# geiger_fixedR5R6.net
KiCad netlist of a schematic drawn in EAGLE
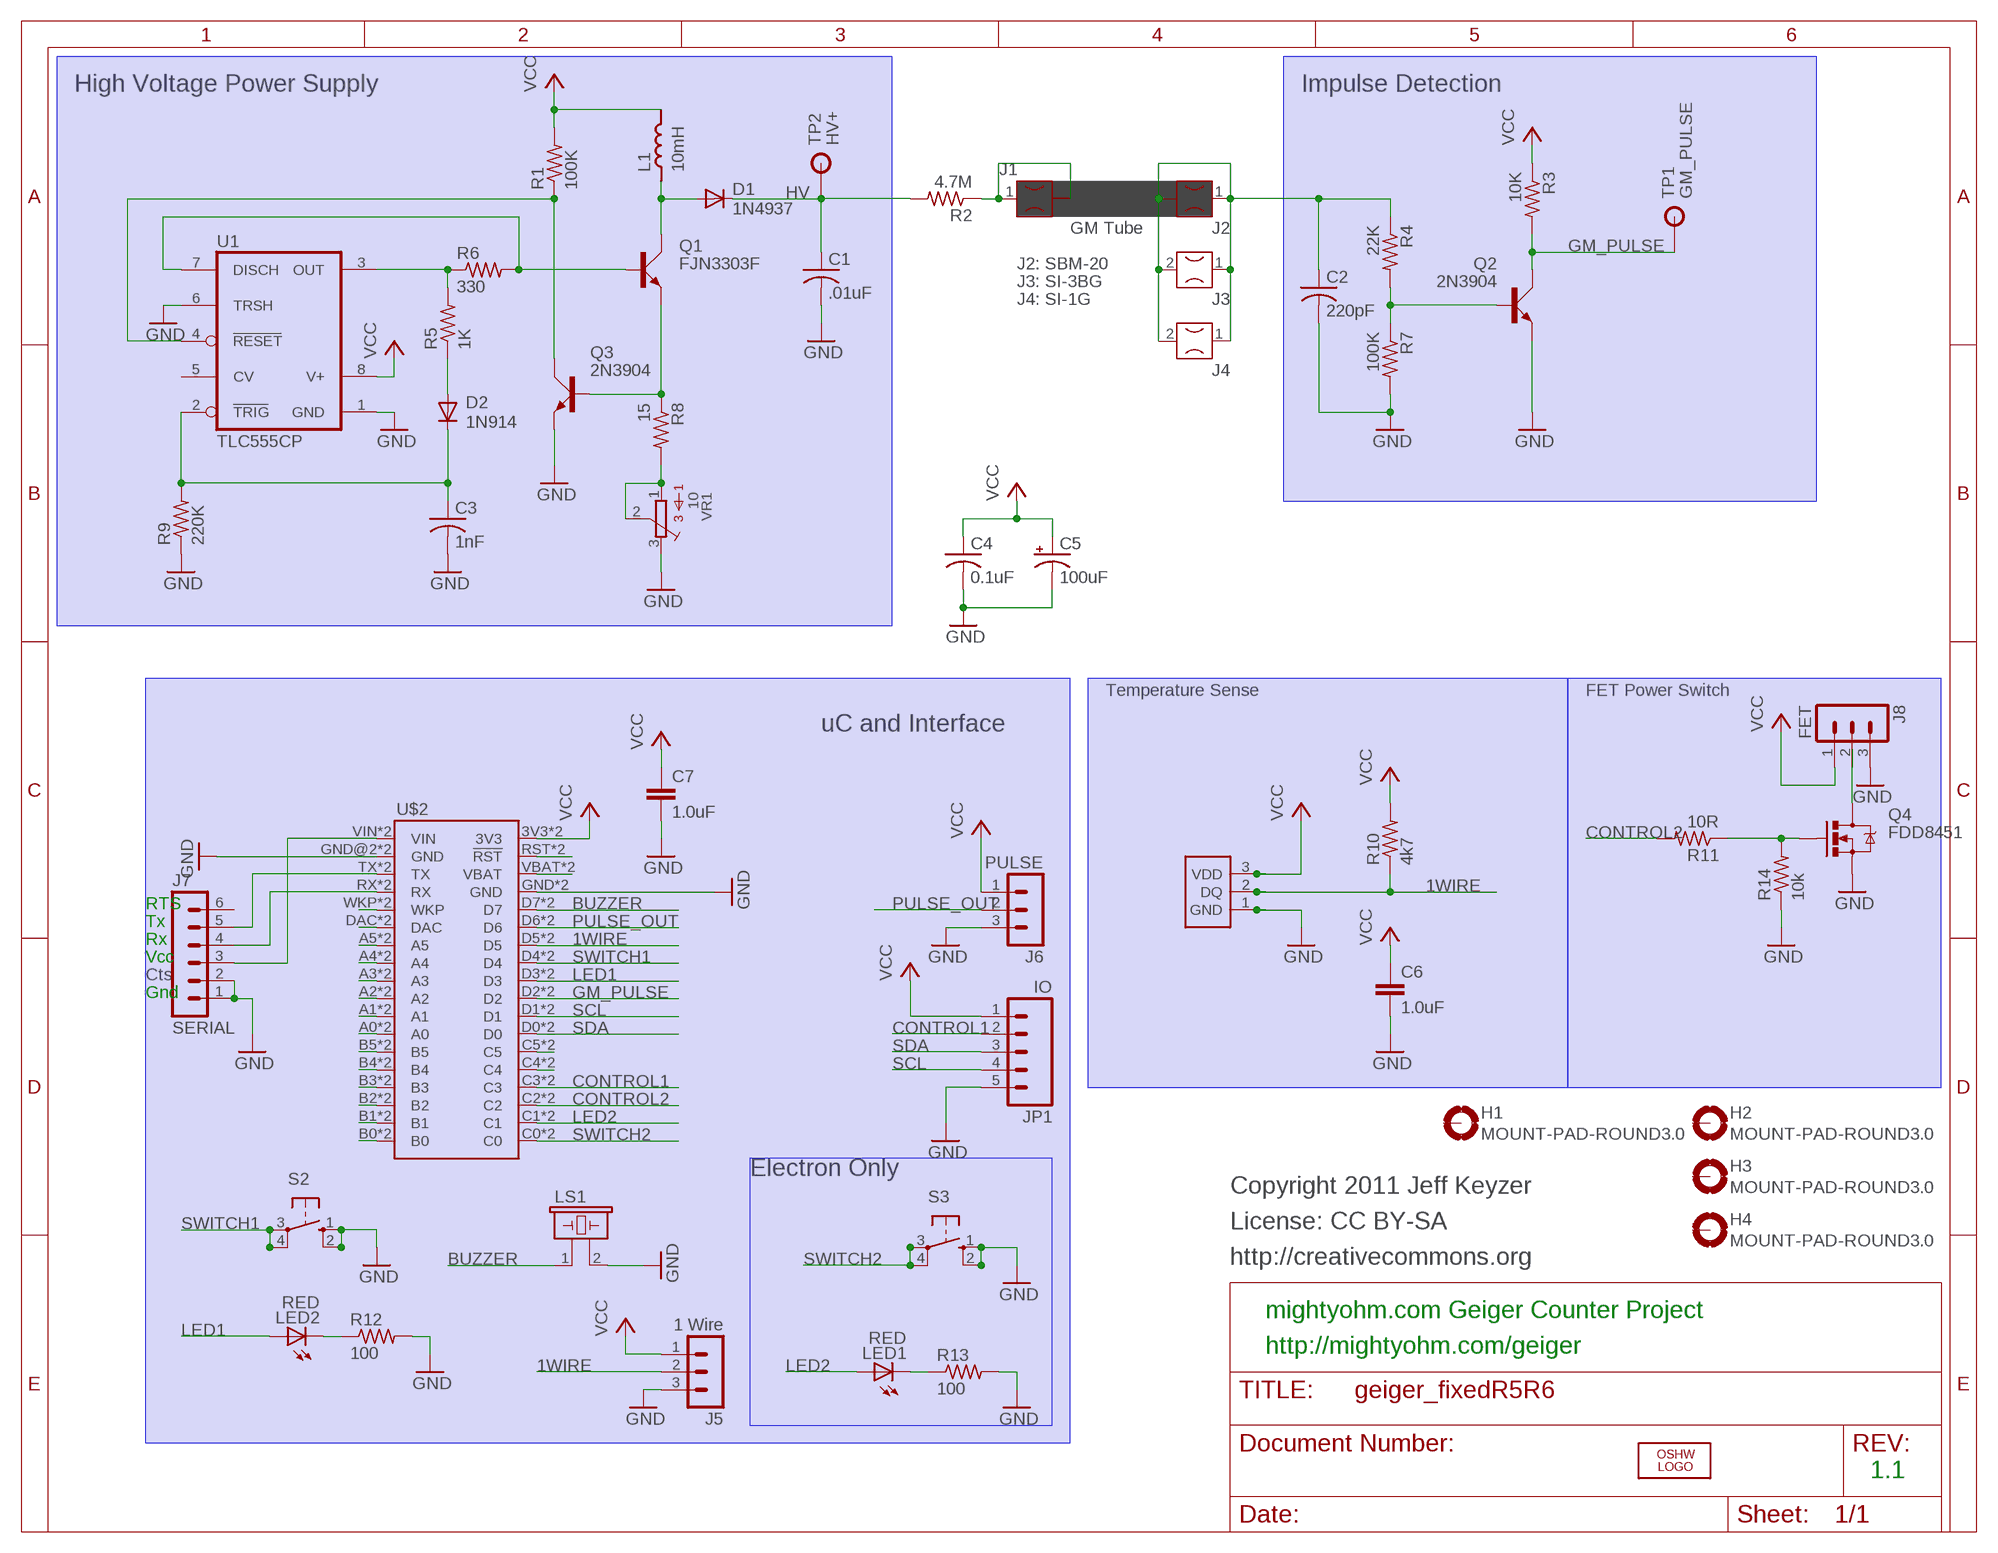
[diagram p0: schematic, sheet 1]

(export (version "E")
  (design (tool "Eeschema 10.0.6"))
  (components
    (comp (ref "C1")
      (value ".01uF")
      (footprint "eagle-import:C102-043X133")
      (libsource (lib "eagle-import") (part "C-US102-043X133"))
    )
    (comp (ref "C2")
      (value "220pF")
      (footprint "eagle-import:C050-030X075")
      (libsource (lib "eagle-import") (part "C-US050-030X075"))
    )
    (comp (ref "C3")
      (value "1nF")
      (footprint "eagle-import:C050-025X075")
      (libsource (lib "eagle-import") (part "C-US050-025X075"))
    )
    (comp (ref "C4")
      (value "0.1uF")
      (footprint "eagle-import:C025-025X050")
      (libsource (lib "eagle-import") (part "C-US025-025X050"))
    )
    (comp (ref "C5")
      (value "100uF")
      (footprint "eagle-import:E2,5-6")
      (libsource (lib "eagle-import") (part "CPOL-USE2.5-6"))
    )
    (comp (ref "C6")
      (value "1.0uF")
      (footprint "eagle-import:0805-CAP")
      (libsource (lib "eagle-import") (part "1.0UF-25V-+80/-20(0805){dblquote}"))
    )
    (comp (ref "C7")
      (value "1.0uF")
      (footprint "eagle-import:0805-CAP")
      (libsource (lib "eagle-import") (part "1.0UF-25V-+80/-20(0805){dblquote}"))
    )
    (comp (ref "D1")
      (value "1N4937")
      (footprint "eagle-import:DO41-10")
      (libsource (lib "eagle-import") (part "1N4933"))
    )
    (comp (ref "D2")
      (value "1N914")
      (footprint "eagle-import:DO35-7")
      (libsource (lib "eagle-import") (part "1N4148DO35-7"))
    )
    (comp (ref "H1")
      (value "MOUNT-PAD-ROUND3.0")
      (footprint "eagle-import:3,0-PAD")
      (libsource (lib "eagle-import") (part "MOUNT-PAD-ROUND3.0"))
    )
    (comp (ref "H2")
      (value "MOUNT-PAD-ROUND3.0")
      (footprint "eagle-import:3,0-PAD")
      (libsource (lib "eagle-import") (part "MOUNT-PAD-ROUND3.0"))
    )
    (comp (ref "H3")
      (value "MOUNT-PAD-ROUND3.0")
      (footprint "eagle-import:3,0-PAD")
      (libsource (lib "eagle-import") (part "MOUNT-PAD-ROUND3.0"))
    )
    (comp (ref "H4")
      (value "MOUNT-PAD-ROUND3.0")
      (footprint "eagle-import:3,0-PAD")
      (libsource (lib "eagle-import") (part "MOUNT-PAD-ROUND3.0"))
    )
    (comp (ref "J1")
      (value "FUSECLIPPCMOUNT")
      (footprint "eagle-import:FUSECLIP_PCMOUNT")
      (libsource (lib "eagle-import") (part "FUSECLIPPCMOUNT"))
    )
    (comp (ref "J2")
      (value "FUSECLIPPCMOUNT")
      (footprint "eagle-import:FUSECLIP_PCMOUNT")
      (libsource (lib "eagle-import") (part "FUSECLIPPCMOUNT"))
    )
    (comp (ref "J3")
      (value "FUSECLIPPCMOUNT")
      (footprint "eagle-import:FUSECLIP_PCMOUNT")
      (libsource (lib "eagle-import") (part "FUSECLIPPCMOUNT"))
    )
    (comp (ref "J4")
      (value "FUSECLIPPCMOUNT")
      (footprint "eagle-import:FUSECLIP_PCMOUNT")
      (libsource (lib "eagle-import") (part "FUSECLIPPCMOUNT"))
    )
    (comp (ref "J5")
      (value "1 Wire")
      (footprint "eagle-import:MA03-1")
      (libsource (lib "eagle-import") (part "MA03-1"))
    )
    (comp (ref "J6")
      (value "PULSE")
      (footprint "eagle-import:MA03-1")
      (libsource (lib "eagle-import") (part "MA03-1"))
    )
    (comp (ref "J7")
      (value "SERIAL")
      (footprint "eagle-import:MA06-1")
      (libsource (lib "eagle-import") (part "MA06-1"))
    )
    (comp (ref "J8")
      (value "FET")
      (footprint "eagle-import:MA03-1")
      (libsource (lib "eagle-import") (part "MA03-1"))
    )
    (comp (ref "JP1")
      (value "IO")
      (footprint "eagle-import:1X05")
      (libsource (lib "eagle-import") (part "M05PTH"))
    )
    (comp (ref "L1")
      (value "10mH")
      (footprint "eagle-import:ELC09D")
      (libsource (lib "eagle-import") (part "INDELC09D"))
    )
    (comp (ref "LED1")
      (value "RED")
      (footprint "eagle-import:LED5MM")
      (libsource (lib "eagle-import") (part "LED5MM"))
    )
    (comp (ref "LED2")
      (value "RED")
      (footprint "eagle-import:LED5MM")
      (libsource (lib "eagle-import") (part "LED5MM"))
    )
    (comp (ref "LOGO1")
      (value "OSHW_LOGO_FILLX0200-NT")
      (footprint "eagle-import:OSHW_FILLX200_NOTEXT")
      (libsource (lib "eagle-import") (part "OSHW_LOGO_FILLX0200-NT"))
    )
    (comp (ref "LS1")
      (value "PIEZO17MM")
      (footprint "eagle-import:PS1740P02E")
      (libsource (lib "eagle-import") (part "PIEZO17MM"))
    )
    (comp (ref "Q1")
      (value "FJN3303F")
      (footprint "eagle-import:TO92C")
      (libsource (lib "eagle-import") (part "2N3704"))
    )
    (comp (ref "Q2")
      (value "2N3904")
      (footprint "eagle-import:TO92D")
      (libsource (lib "eagle-import") (part "2N3904"))
    )
    (comp (ref "Q3")
      (value "2N3904")
      (footprint "eagle-import:TO92D")
      (libsource (lib "eagle-import") (part "2N3904"))
    )
    (comp (ref "Q4")
      (value "FDD8451")
      (footprint "eagle-import:DPAK")
      (libsource (lib "eagle-import") (part "MOSFET-NCHANNELFDD8780"))
    )
    (comp (ref "R1")
      (value "100K")
      (footprint "eagle-import:0207_10")
      (libsource (lib "eagle-import") (part "R-US_0207/10"))
    )
    (comp (ref "R2")
      (value "4.7M")
      (footprint "eagle-import:0207_10")
      (libsource (lib "eagle-import") (part "R-US_0207/10"))
    )
    (comp (ref "R3")
      (value "10K")
      (footprint "eagle-import:0207_10")
      (libsource (lib "eagle-import") (part "R-US_0207/10"))
    )
    (comp (ref "R4")
      (value "22K")
      (footprint "eagle-import:0207_10")
      (libsource (lib "eagle-import") (part "R-US_0207/10"))
    )
    (comp (ref "R5")
      (value "1K")
      (footprint "eagle-import:0207_10")
      (libsource (lib "eagle-import") (part "R-US_0207/10"))
    )
    (comp (ref "R6")
      (value "330")
      (footprint "eagle-import:0207_10")
      (libsource (lib "eagle-import") (part "R-US_0207/10"))
    )
    (comp (ref "R7")
      (value "100K")
      (footprint "eagle-import:0207_10")
      (libsource (lib "eagle-import") (part "R-US_0207/10"))
    )
    (comp (ref "R8")
      (value "15")
      (footprint "eagle-import:0207_10")
      (libsource (lib "eagle-import") (part "R-US_0207/10"))
    )
    (comp (ref "R9")
      (value "220K")
      (footprint "eagle-import:0207_10")
      (libsource (lib "eagle-import") (part "R-US_0207/10"))
    )
    (comp (ref "R10")
      (value "4k7")
      (footprint "eagle-import:R0805")
      (libsource (lib "eagle-import") (part "R-US_R0805"))
    )
    (comp (ref "R11")
      (value "10R")
      (footprint "eagle-import:R0805")
      (libsource (lib "eagle-import") (part "R-US_R0805"))
    )
    (comp (ref "R12")
      (value "100")
      (footprint "eagle-import:R0805")
      (libsource (lib "eagle-import") (part "R-US_R0805"))
    )
    (comp (ref "R13")
      (value "100")
      (footprint "eagle-import:R0805")
      (libsource (lib "eagle-import") (part "R-US_R0805"))
    )
    (comp (ref "R14")
      (value "10k")
      (footprint "eagle-import:R0805")
      (libsource (lib "eagle-import") (part "R-US_R0805"))
    )
    (comp (ref "S1")
      (value "DB18B20+")
      (footprint "eagle-import:TO-92-TRIANGLE")
      (libsource (lib "eagle-import") (part "SENSOR-DS18B20"))
    )
    (comp (ref "S2")
      (value "10-XX")
      (footprint "eagle-import:B3F-10XX")
      (libsource (lib "eagle-import") (part "10-XX"))
    )
    (comp (ref "S3")
      (value "10-XX")
      (footprint "eagle-import:B3F-10XX")
      (libsource (lib "eagle-import") (part "10-XX"))
    )
    (comp (ref "TP1")
      (value "GM_PULSE")
      (footprint "eagle-import:TP_PTH")
      (libsource (lib "eagle-import") (part "TPPTH"))
    )
    (comp (ref "TP2")
      (value "HV+")
      (footprint "eagle-import:TP_PTH")
      (libsource (lib "eagle-import") (part "TPPTH"))
    )
    (comp (ref "U$2")
      (value "ELECTRONDUALNAMED")
      (footprint "eagle-import:ELECTRON_SIMPLE_SILK_NAMES_DUAL")
      (libsource (lib "eagle-import") (part "ELECTRONDUALNAMED"))
    )
    (comp (ref "U1")
      (value "TLC555CP")
      (footprint "eagle-import:DIL08")
      (libsource (lib "eagle-import") (part "ICM7555"))
    )
    (comp (ref "VR1")
      (value "10")
      (footprint "eagle-import:3386P")
      (libsource (lib "eagle-import") (part "3386-P"))
    )
  )
  (nets
    (net (code "1") (name "/1WIRE") (class "Default")
      (node (ref "J5") (pin "2") (pinfunction "2_2") (pintype "passive"))
      (node (ref "R10") (pin "1") (pinfunction "1_1") (pintype "passive"))
      (node (ref "S1") (pin "2") (pinfunction "DQ_2") (pintype "bidirectional"))
      (node (ref "U$2") (pin "D5") (pinfunction "D5_D5") (pintype "bidirectional"))
      (node (ref "U$2") (pin "D5_1") (pinfunction "D5_D5_1") (pintype "bidirectional"))
    )
    (net (code "2") (name "/BUZZER") (class "Default")
      (node (ref "LS1") (pin "1") (pinfunction "1_1") (pintype "passive"))
      (node (ref "U$2") (pin "D7") (pinfunction "D7_D7") (pintype "bidirectional"))
      (node (ref "U$2") (pin "D7_1") (pinfunction "D7_D7_1") (pintype "bidirectional"))
    )
    (net (code "3") (name "/CONTROL1") (class "Default")
      (node (ref "JP1") (pin "2") (pinfunction "2_2") (pintype "passive"))
      (node (ref "U$2") (pin "C3") (pinfunction "C3_C3") (pintype "bidirectional"))
      (node (ref "U$2") (pin "C3_1") (pinfunction "C3_C3_1") (pintype "bidirectional"))
    )
    (net (code "4") (name "/CONTROL2") (class "Default")
      (node (ref "R11") (pin "2") (pinfunction "2_2") (pintype "passive"))
      (node (ref "U$2") (pin "C2") (pinfunction "C2_C2") (pintype "bidirectional"))
      (node (ref "U$2") (pin "C2_1") (pinfunction "C2_C2_1") (pintype "bidirectional"))
    )
    (net (code "5") (name "/GM_PULSE") (class "Default")
      (node (ref "Q2") (pin "C") (pinfunction "C_C") (pintype "passive"))
      (node (ref "R3") (pin "2") (pinfunction "2_2") (pintype "passive"))
      (node (ref "TP1") (pin "P$1") (pinfunction "TP_P$1") (pintype "bidirectional"))
      (node (ref "U$2") (pin "D2") (pinfunction "D2_D2") (pintype "bidirectional"))
      (node (ref "U$2") (pin "D2_1") (pinfunction "D2_D2_1") (pintype "bidirectional"))
    )
    (net (code "6") (name "/HV") (class "Default")
      (node (ref "C1") (pin "1") (pinfunction "1_1") (pintype "passive"))
      (node (ref "D1") (pin "C") (pinfunction "C_C") (pintype "passive"))
      (node (ref "R2") (pin "2") (pinfunction "2_2") (pintype "passive"))
      (node (ref "TP2") (pin "P$1") (pinfunction "TP_P$1") (pintype "bidirectional"))
    )
    (net (code "7") (name "/LED1") (class "Default")
      (node (ref "LED2") (pin "A") (pinfunction "A_A") (pintype "passive"))
      (node (ref "U$2") (pin "D3") (pinfunction "D3_D3") (pintype "bidirectional"))
      (node (ref "U$2") (pin "D3_1") (pinfunction "D3_D3_1") (pintype "bidirectional"))
    )
    (net (code "8") (name "/LED2") (class "Default")
      (node (ref "LED1") (pin "A") (pinfunction "A_A") (pintype "passive"))
      (node (ref "U$2") (pin "C1") (pinfunction "C1_C1") (pintype "bidirectional"))
      (node (ref "U$2") (pin "C1_1") (pinfunction "C1_C1_1") (pintype "bidirectional"))
    )
    (net (code "9") (name "/PULSE_OUT") (class "Default")
      (node (ref "J6") (pin "2") (pinfunction "2_2") (pintype "passive"))
      (node (ref "U$2") (pin "D6") (pinfunction "D6_D6") (pintype "bidirectional"))
      (node (ref "U$2") (pin "D6_1") (pinfunction "D6_D6_1") (pintype "bidirectional"))
    )
    (net (code "10") (name "/SCL") (class "Default")
      (node (ref "JP1") (pin "4") (pinfunction "4_4") (pintype "passive"))
      (node (ref "U$2") (pin "D1") (pinfunction "D1_D1") (pintype "bidirectional"))
      (node (ref "U$2") (pin "D1_1") (pinfunction "D1_D1_1") (pintype "bidirectional"))
    )
    (net (code "11") (name "/SDA") (class "Default")
      (node (ref "JP1") (pin "3") (pinfunction "3_3") (pintype "passive"))
      (node (ref "U$2") (pin "D0") (pinfunction "D0_D0") (pintype "bidirectional"))
      (node (ref "U$2") (pin "D0_1") (pinfunction "D0_D0_1") (pintype "bidirectional"))
    )
    (net (code "12") (name "/SWITCH1") (class "Default")
      (node (ref "S2") (pin "3") (pinfunction "P_3") (pintype "passive"))
      (node (ref "S2") (pin "4") (pinfunction "P1_4") (pintype "passive"))
      (node (ref "U$2") (pin "D4") (pinfunction "D4_D4") (pintype "bidirectional"))
      (node (ref "U$2") (pin "D4_1") (pinfunction "D4_D4_1") (pintype "bidirectional"))
    )
    (net (code "13") (name "/SWITCH2") (class "Default")
      (node (ref "S3") (pin "3") (pinfunction "P_3") (pintype "passive"))
      (node (ref "S3") (pin "4") (pinfunction "P1_4") (pintype "passive"))
      (node (ref "U$2") (pin "C0") (pinfunction "C0_C0") (pintype "bidirectional"))
      (node (ref "U$2") (pin "C0_1") (pinfunction "C0_C0_1") (pintype "bidirectional"))
    )
    (net (code "14") (name "GND") (class "Default")
      (node (ref "C1") (pin "2") (pinfunction "2_2") (pintype "passive"))
      (node (ref "C2") (pin "2") (pinfunction "2_2") (pintype "passive"))
      (node (ref "C3") (pin "2") (pinfunction "2_2") (pintype "passive"))
      (node (ref "C4") (pin "2") (pinfunction "2_2") (pintype "passive"))
      (node (ref "C5") (pin "-") (pinfunction "-_-") (pintype "passive"))
      (node (ref "C6") (pin "2") (pinfunction "2_2") (pintype "passive"))
      (node (ref "C7") (pin "2") (pinfunction "2_2") (pintype "passive"))
      (node (ref "J5") (pin "3") (pinfunction "3_3") (pintype "passive"))
      (node (ref "J6") (pin "3") (pinfunction "3_3") (pintype "passive"))
      (node (ref "J7") (pin "1") (pinfunction "1_1") (pintype "passive"))
      (node (ref "J7") (pin "2") (pinfunction "2_2") (pintype "passive"))
      (node (ref "J8") (pin "3") (pinfunction "3_3") (pintype "passive"))
      (node (ref "JP1") (pin "5") (pinfunction "5_5") (pintype "passive"))
      (node (ref "LS1") (pin "2") (pinfunction "2_2") (pintype "passive"))
      (node (ref "Q2") (pin "E") (pinfunction "E_E") (pintype "passive"))
      (node (ref "Q3") (pin "E") (pinfunction "E_E") (pintype "passive"))
      (node (ref "Q4") (pin "3") (pinfunction "S_3") (pintype "passive"))
      (node (ref "R12") (pin "2") (pinfunction "2_2") (pintype "passive"))
      (node (ref "R13") (pin "2") (pinfunction "2_2") (pintype "passive"))
      (node (ref "R14") (pin "1") (pinfunction "1_1") (pintype "passive"))
      (node (ref "R7") (pin "2") (pinfunction "2_2") (pintype "passive"))
      (node (ref "R9") (pin "1") (pinfunction "1_1") (pintype "passive"))
      (node (ref "S1") (pin "1") (pinfunction "GND_1") (pintype "bidirectional"))
      (node (ref "S2") (pin "1") (pinfunction "S_1") (pintype "passive"))
      (node (ref "S2") (pin "2") (pinfunction "S1_2") (pintype "passive"))
      (node (ref "S3") (pin "1") (pinfunction "S_1") (pintype "passive"))
      (node (ref "S3") (pin "2") (pinfunction "S1_2") (pintype "passive"))
      (node (ref "U$2") (pin "GND") (pinfunction "GND_GND") (pintype "power_in"))
      (node (ref "U$2") (pin "GND@2") (pinfunction "GND_GND@2") (pintype "power_in"))
      (node (ref "U$2") (pin "GND_1") (pinfunction "GND_GND_1") (pintype "power_in"))
      (node (ref "U$2") (pin "GND_1B") (pinfunction "GND_GND_1B") (pintype "power_in"))
      (node (ref "U1") (pin "1") (pinfunction "GND_1") (pintype "power_in"))
      (node (ref "U1") (pin "6") (pinfunction "TRSH_6") (pintype "input"))
      (node (ref "VR1") (pin "3") (pinfunction "3_3") (pintype "passive"))
    )
    (net (code "15") (name "Net-(C2-Pad1)") (class "Default")
      (node (ref "C2") (pin "1") (pinfunction "1_1") (pintype "passive"))
      (node (ref "J2") (pin "1") (pinfunction "1_1") (pintype "bidirectional"))
      (node (ref "J2") (pin "2") (pinfunction "2_2") (pintype "bidirectional"))
      (node (ref "J3") (pin "1") (pinfunction "1_1") (pintype "bidirectional"))
      (node (ref "J3") (pin "2") (pinfunction "2_2") (pintype "bidirectional"))
      (node (ref "J4") (pin "1") (pinfunction "1_1") (pintype "bidirectional"))
      (node (ref "J4") (pin "2") (pinfunction "2_2") (pintype "bidirectional"))
      (node (ref "R4") (pin "1") (pinfunction "1_1") (pintype "passive"))
    )
    (net (code "16") (name "Net-(D1-PadA)") (class "Default")
      (node (ref "D1") (pin "A") (pinfunction "A_A") (pintype "passive"))
      (node (ref "L1") (pin "1") (pinfunction "1_1") (pintype "passive"))
      (node (ref "Q1") (pin "C") (pinfunction "C_C") (pintype "passive"))
    )
    (net (code "17") (name "Net-(D2-PadA)") (class "Default")
      (node (ref "D2") (pin "A") (pinfunction "A_A") (pintype "passive"))
      (node (ref "R5") (pin "1") (pinfunction "1_1") (pintype "passive"))
    )
    (net (code "18") (name "Net-(J1-Pad1)") (class "Default")
      (node (ref "J1") (pin "1") (pinfunction "1_1") (pintype "bidirectional"))
      (node (ref "J1") (pin "2") (pinfunction "2_2") (pintype "bidirectional"))
      (node (ref "R2") (pin "1") (pinfunction "1_1") (pintype "passive"))
    )
    (net (code "19") (name "Net-(J7-Pad3)") (class "Default")
      (node (ref "J7") (pin "3") (pinfunction "3_3") (pintype "passive"))
      (node (ref "U$2") (pin "VIN") (pinfunction "VIN_VIN") (pintype "power_in"))
      (node (ref "U$2") (pin "VIN_1B") (pinfunction "VIN_VIN_1B") (pintype "power_in"))
    )
    (net (code "20") (name "Net-(J7-Pad4)") (class "Default")
      (node (ref "J7") (pin "4") (pinfunction "4_4") (pintype "passive"))
      (node (ref "U$2") (pin "RX") (pinfunction "RX_RX") (pintype "bidirectional"))
      (node (ref "U$2") (pin "RX_1") (pinfunction "RX_RX_1") (pintype "bidirectional"))
    )
    (net (code "21") (name "Net-(J7-Pad5)") (class "Default")
      (node (ref "J7") (pin "5") (pinfunction "5_5") (pintype "passive"))
      (node (ref "U$2") (pin "TX") (pinfunction "TX_TX") (pintype "bidirectional"))
      (node (ref "U$2") (pin "TX_1") (pinfunction "TX_TX_1") (pintype "bidirectional"))
    )
    (net (code "22") (name "Net-(LED1-C)") (class "Default")
      (node (ref "LED1") (pin "K") (pinfunction "C_K") (pintype "passive"))
      (node (ref "R13") (pin "1") (pinfunction "1_1") (pintype "passive"))
    )
    (net (code "23") (name "Net-(LED2-C)") (class "Default")
      (node (ref "LED2") (pin "K") (pinfunction "C_K") (pintype "passive"))
      (node (ref "R12") (pin "1") (pinfunction "1_1") (pintype "passive"))
    )
    (net (code "24") (name "Net-(Q1-PadE)") (class "Default")
      (node (ref "Q1") (pin "E") (pinfunction "E_E") (pintype "passive"))
      (node (ref "Q3") (pin "B") (pinfunction "B_B") (pintype "passive"))
      (node (ref "R8") (pin "1") (pinfunction "1_1") (pintype "passive"))
    )
    (net (code "25") (name "Net-(Q2-PadB)") (class "Default")
      (node (ref "Q2") (pin "B") (pinfunction "B_B") (pintype "passive"))
      (node (ref "R4") (pin "2") (pinfunction "2_2") (pintype "passive"))
      (node (ref "R7") (pin "1") (pinfunction "1_1") (pintype "passive"))
    )
    (net (code "26") (name "Net-(Q4-D)") (class "Default")
      (node (ref "J8") (pin "2") (pinfunction "2_2") (pintype "passive"))
      (node (ref "Q4") (pin "4") (pinfunction "D_4") (pintype "passive"))
    )
    (net (code "27") (name "Net-(Q4-G)") (class "Default")
      (node (ref "Q4") (pin "1") (pinfunction "G_1") (pintype "passive"))
      (node (ref "R11") (pin "1") (pinfunction "1_1") (pintype "passive"))
      (node (ref "R14") (pin "2") (pinfunction "2_2") (pintype "passive"))
    )
    (net (code "28") (name "Net-(R8-Pad2)") (class "Default")
      (node (ref "R8") (pin "2") (pinfunction "2_2") (pintype "passive"))
      (node (ref "VR1") (pin "1") (pinfunction "1_1") (pintype "passive"))
      (node (ref "VR1") (pin "2") (pinfunction "2_2") (pintype "passive"))
    )
    (net (code "29") (name "Net-(U$2-A0-PadA0_1)") (class "Default")
      (node (ref "U$2") (pin "A0") (pinfunction "A0_A0") (pintype "bidirectional"))
      (node (ref "U$2") (pin "A0_1") (pinfunction "A0_A0_1") (pintype "bidirectional"))
    )
    (net (code "30") (name "Net-(U$2-A1-PadA1_1)") (class "Default")
      (node (ref "U$2") (pin "A1") (pinfunction "A1_A1") (pintype "bidirectional"))
      (node (ref "U$2") (pin "A1_1") (pinfunction "A1_A1_1") (pintype "bidirectional"))
    )
    (net (code "31") (name "Net-(U$2-A2-PadA2_1)") (class "Default")
      (node (ref "U$2") (pin "A2") (pinfunction "A2_A2") (pintype "bidirectional"))
      (node (ref "U$2") (pin "A2_1") (pinfunction "A2_A2_1") (pintype "bidirectional"))
    )
    (net (code "32") (name "Net-(U$2-A3-PadA3_1)") (class "Default")
      (node (ref "U$2") (pin "A3") (pinfunction "A3_A3") (pintype "bidirectional"))
      (node (ref "U$2") (pin "A3_1") (pinfunction "A3_A3_1") (pintype "bidirectional"))
    )
    (net (code "33") (name "Net-(U$2-A4-PadA4_1)") (class "Default")
      (node (ref "U$2") (pin "A4") (pinfunction "A4_A4") (pintype "bidirectional"))
      (node (ref "U$2") (pin "A4_1") (pinfunction "A4_A4_1") (pintype "bidirectional"))
    )
    (net (code "34") (name "Net-(U$2-A5-PadA5_1)") (class "Default")
      (node (ref "U$2") (pin "A5") (pinfunction "A5_A5") (pintype "bidirectional"))
      (node (ref "U$2") (pin "A5_1") (pinfunction "A5_A5_1") (pintype "bidirectional"))
    )
    (net (code "35") (name "Net-(U$2-B0-PadB0_1)") (class "Default")
      (node (ref "U$2") (pin "B0") (pinfunction "B0_B0") (pintype "bidirectional"))
      (node (ref "U$2") (pin "B0_1") (pinfunction "B0_B0_1") (pintype "bidirectional"))
    )
    (net (code "36") (name "Net-(U$2-B1-PadB1_1)") (class "Default")
      (node (ref "U$2") (pin "B1") (pinfunction "B1_B1") (pintype "bidirectional"))
      (node (ref "U$2") (pin "B1_1") (pinfunction "B1_B1_1") (pintype "bidirectional"))
    )
    (net (code "37") (name "Net-(U$2-B2-PadB2_1)") (class "Default")
      (node (ref "U$2") (pin "B2") (pinfunction "B2_B2") (pintype "bidirectional"))
      (node (ref "U$2") (pin "B2_1") (pinfunction "B2_B2_1") (pintype "bidirectional"))
    )
    (net (code "38") (name "Net-(U$2-B3-PadB3_1)") (class "Default")
      (node (ref "U$2") (pin "B3") (pinfunction "B3_B3") (pintype "bidirectional"))
      (node (ref "U$2") (pin "B3_1") (pinfunction "B3_B3_1") (pintype "bidirectional"))
    )
    (net (code "39") (name "Net-(U$2-B4-PadB4_1)") (class "Default")
      (node (ref "U$2") (pin "B4") (pinfunction "B4_B4") (pintype "bidirectional"))
      (node (ref "U$2") (pin "B4_1") (pinfunction "B4_B4_1") (pintype "bidirectional"))
    )
    (net (code "40") (name "Net-(U$2-B5-PadB5_1)") (class "Default")
      (node (ref "U$2") (pin "B5") (pinfunction "B5_B5") (pintype "bidirectional"))
      (node (ref "U$2") (pin "B5_1") (pinfunction "B5_B5_1") (pintype "bidirectional"))
    )
    (net (code "41") (name "Net-(U$2-C4-PadC4_1)") (class "Default")
      (node (ref "U$2") (pin "C4") (pinfunction "C4_C4") (pintype "bidirectional"))
      (node (ref "U$2") (pin "C4_1") (pinfunction "C4_C4_1") (pintype "bidirectional"))
    )
    (net (code "42") (name "Net-(U$2-C5-PadC5_1)") (class "Default")
      (node (ref "U$2") (pin "C5") (pinfunction "C5_C5") (pintype "bidirectional"))
      (node (ref "U$2") (pin "C5_1") (pinfunction "C5_C5_1") (pintype "bidirectional"))
    )
    (net (code "43") (name "Net-(U$2-DAC-PadDAC_1)") (class "Default")
      (node (ref "U$2") (pin "DAC") (pinfunction "DAC_DAC") (pintype "bidirectional"))
      (node (ref "U$2") (pin "DAC_1") (pinfunction "DAC_DAC_1") (pintype "bidirectional"))
    )
    (net (code "44") (name "Net-(U$2-PadVBAT)") (class "Default")
      (node (ref "U$2") (pin "VBAT") (pinfunction "VBAT_VBAT") (pintype "passive"))
      (node (ref "U$2") (pin "VBATT_1") (pinfunction "VBAT_VBATT_1") (pintype "passive"))
    )
    (net (code "45") (name "Net-(U$2-PadWKP)") (class "Default")
      (node (ref "U$2") (pin "WKP") (pinfunction "WKP_WKP") (pintype "bidirectional"))
      (node (ref "U$2") (pin "WKP_1") (pinfunction "WKP_WKP_1") (pintype "bidirectional"))
    )
    (net (code "46") (name "Net-(U$2-~{RST}-PadRST)") (class "Default")
      (node (ref "U$2") (pin "RST") (pinfunction "~{RST}_RST") (pintype "bidirectional"))
      (node (ref "U$2") (pin "RST_1") (pinfunction "~{RST}_RST_1") (pintype "bidirectional"))
    )
    (net (code "47") (name "Net-(U1-DISCH)") (class "Default")
      (node (ref "Q1") (pin "B") (pinfunction "B_B") (pintype "passive"))
      (node (ref "R6") (pin "2") (pinfunction "2_2") (pintype "passive"))
      (node (ref "U1") (pin "7") (pinfunction "DISCH_7") (pintype "input"))
    )
    (net (code "48") (name "Net-(U1-OUT)") (class "Default")
      (node (ref "R5") (pin "2") (pinfunction "2_2") (pintype "passive"))
      (node (ref "R6") (pin "1") (pinfunction "1_1") (pintype "passive"))
      (node (ref "U1") (pin "3") (pinfunction "OUT_3") (pintype "output"))
    )
    (net (code "49") (name "Net-(U1-RESET)") (class "Default")
      (node (ref "Q3") (pin "C") (pinfunction "C_C") (pintype "passive"))
      (node (ref "R1") (pin "1") (pinfunction "1_1") (pintype "passive"))
      (node (ref "U1") (pin "4") (pinfunction "RESET_4") (pintype "input"))
    )
    (net (code "50") (name "Net-(U1-TRIG)") (class "Default")
      (node (ref "C3") (pin "1") (pinfunction "1_1") (pintype "passive"))
      (node (ref "D2") (pin "C") (pinfunction "C_C") (pintype "passive"))
      (node (ref "R9") (pin "2") (pinfunction "2_2") (pintype "passive"))
      (node (ref "U1") (pin "2") (pinfunction "TRIG_2") (pintype "bidirectional"))
    )
    (net (code "51") (name "VCC") (class "Default")
      (node (ref "C4") (pin "1") (pinfunction "1_1") (pintype "passive"))
      (node (ref "C5") (pin "+") (pinfunction "+_+") (pintype "passive"))
      (node (ref "C6") (pin "1") (pinfunction "1_1") (pintype "passive"))
      (node (ref "C7") (pin "1") (pinfunction "1_1") (pintype "passive"))
      (node (ref "J5") (pin "1") (pinfunction "1_1") (pintype "passive"))
      (node (ref "J6") (pin "1") (pinfunction "1_1") (pintype "passive"))
      (node (ref "J8") (pin "1") (pinfunction "1_1") (pintype "passive"))
      (node (ref "JP1") (pin "1") (pinfunction "1_1") (pintype "passive"))
      (node (ref "L1") (pin "2") (pinfunction "2_2") (pintype "passive"))
      (node (ref "R1") (pin "2") (pinfunction "2_2") (pintype "passive"))
      (node (ref "R10") (pin "2") (pinfunction "2_2") (pintype "passive"))
      (node (ref "R3") (pin "1") (pinfunction "1_1") (pintype "passive"))
      (node (ref "S1") (pin "3") (pinfunction "VDD_3") (pintype "bidirectional"))
      (node (ref "U$2") (pin "3V3") (pinfunction "3V3_3V3") (pintype "power_in"))
      (node (ref "U$2") (pin "3V3_1") (pinfunction "3V3_3V3_1") (pintype "power_in"))
      (node (ref "U1") (pin "8") (pinfunction "V+_8") (pintype "power_in"))
    )
    (net (code "52") (name "unconnected-(H1-MOUNT-PadB3,0)") (class "Default")
      (node (ref "H1") (pin "B3,0") (pinfunction "MOUNT_B3,0") (pintype "passive"))
    )
    (net (code "53") (name "unconnected-(H2-MOUNT-PadB3,0)") (class "Default")
      (node (ref "H2") (pin "B3,0") (pinfunction "MOUNT_B3,0") (pintype "passive"))
    )
    (net (code "54") (name "unconnected-(H3-MOUNT-PadB3,0)") (class "Default")
      (node (ref "H3") (pin "B3,0") (pinfunction "MOUNT_B3,0") (pintype "passive"))
    )
    (net (code "55") (name "unconnected-(H4-MOUNT-PadB3,0)") (class "Default")
      (node (ref "H4") (pin "B3,0") (pinfunction "MOUNT_B3,0") (pintype "passive"))
    )
    (net (code "56") (name "unconnected-(J7-Pad6)") (class "Default")
      (node (ref "J7") (pin "6") (pinfunction "6_6") (pintype "passive"))
    )
    (net (code "57") (name "unconnected-(U1-CV-Pad5)") (class "Default")
      (node (ref "U1") (pin "5") (pinfunction "CV_5") (pintype "passive"))
    )
  )
)
